# Sheet3.net
KiCad netlist of a schematic drawn in Altium Designer
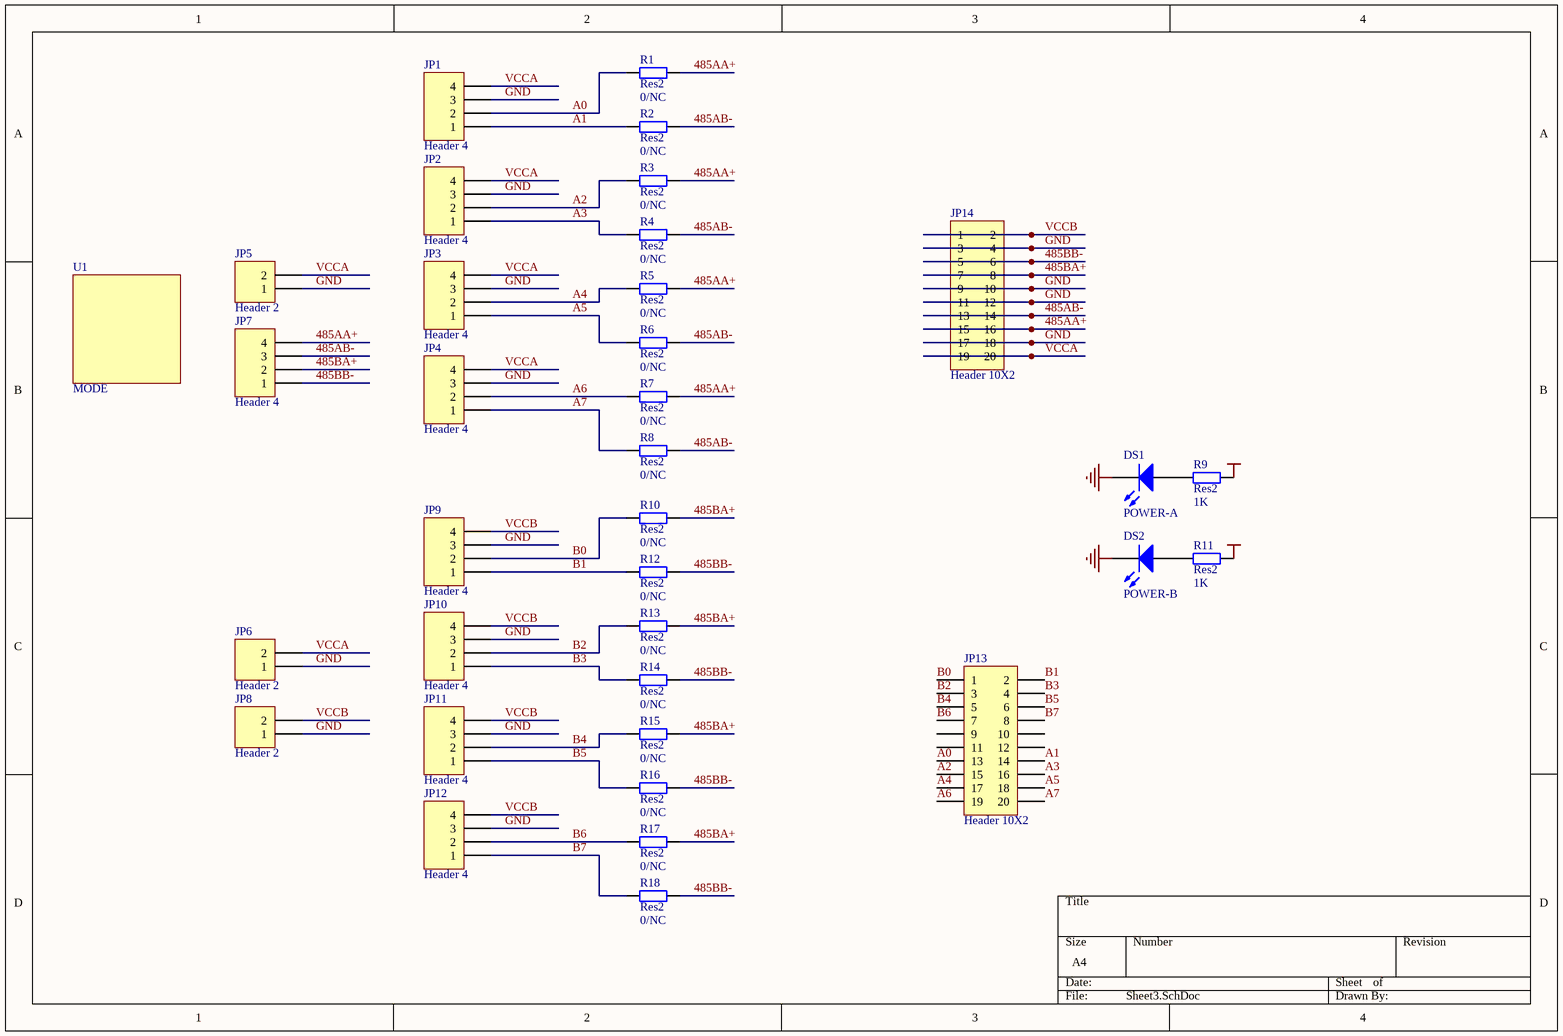
[diagram p0: Sheet3.SchDoc]

(export (version "E")
  (design (tool "Eeschema 10.0.6"))
  (components
    (comp (ref "DS1")
      (value "POWER-A")
      (footprint "SMD _LED")
      (description "Typical BLUE SiC LED")
      (fields (field (name "PUBLISHER") "Altium Limited"))
      (libsource (lib "Miscellaneous Devices") (part "LED3"))
    )
    (comp (ref "DS2")
      (value "POWER-B")
      (footprint "SMD _LED")
      (description "Typical BLUE SiC LED")
      (fields (field (name "PUBLISHER") "Altium Limited"))
      (libsource (lib "Miscellaneous Devices") (part "LED3"))
    )
    (comp (ref "JP1")
      (value "Header 4")
      (footprint "duanzi-4")
      (description "Header, 4-Pin")
      (fields (field (name "PUBLISHER") "Altium Limited"))
      (libsource (lib "Miscellaneous Connectors") (part "Header 4"))
    )
    (comp (ref "JP2")
      (value "Header 4")
      (footprint "duanzi-4")
      (description "Header, 4-Pin")
      (fields (field (name "PUBLISHER") "Altium Limited"))
      (libsource (lib "Miscellaneous Connectors") (part "Header 4"))
    )
    (comp (ref "JP3")
      (value "Header 4")
      (footprint "duanzi-4")
      (description "Header, 4-Pin")
      (fields (field (name "PUBLISHER") "Altium Limited"))
      (libsource (lib "Miscellaneous Connectors") (part "Header 4"))
    )
    (comp (ref "JP4")
      (value "Header 4")
      (footprint "duanzi-4")
      (description "Header, 4-Pin")
      (fields (field (name "PUBLISHER") "Altium Limited"))
      (libsource (lib "Miscellaneous Connectors") (part "Header 4"))
    )
    (comp (ref "JP5")
      (value "Header 2")
      (footprint "duanzi-2")
      (description "Header, 2-Pin")
      (fields (field (name "PUBLISHER") "Altium Limited"))
      (libsource (lib "Miscellaneous Connectors") (part "Header 2"))
    )
    (comp (ref "JP6")
      (value "Header 2")
      (footprint "duanzi-2")
      (description "Header, 2-Pin")
      (fields (field (name "PUBLISHER") "Altium Limited"))
      (libsource (lib "Miscellaneous Connectors") (part "Header 2"))
    )
    (comp (ref "JP7")
      (value "Header 4")
      (footprint "duanzi-4")
      (description "Header, 4-Pin")
      (fields (field (name "PUBLISHER") "Altium Limited"))
      (libsource (lib "Miscellaneous Connectors") (part "Header 4"))
    )
    (comp (ref "JP8")
      (value "Header 2")
      (footprint "duanzi-2")
      (description "Header, 2-Pin")
      (fields (field (name "PUBLISHER") "Altium Limited"))
      (libsource (lib "Miscellaneous Connectors") (part "Header 2"))
    )
    (comp (ref "JP9")
      (value "Header 4")
      (footprint "duanzi-4")
      (description "Header, 4-Pin")
      (fields (field (name "PUBLISHER") "Altium Limited"))
      (libsource (lib "Miscellaneous Connectors") (part "Header 4"))
    )
    (comp (ref "JP10")
      (value "Header 4")
      (footprint "duanzi-4")
      (description "Header, 4-Pin")
      (fields (field (name "PUBLISHER") "Altium Limited"))
      (libsource (lib "Miscellaneous Connectors") (part "Header 4"))
    )
    (comp (ref "JP11")
      (value "Header 4")
      (footprint "duanzi-4")
      (description "Header, 4-Pin")
      (fields (field (name "PUBLISHER") "Altium Limited"))
      (libsource (lib "Miscellaneous Connectors") (part "Header 4"))
    )
    (comp (ref "JP12")
      (value "Header 4")
      (footprint "duanzi-4")
      (description "Header, 4-Pin")
      (fields (field (name "PUBLISHER") "Altium Limited"))
      (libsource (lib "Miscellaneous Connectors") (part "Header 4"))
    )
    (comp (ref "JP13")
      (value "Header 10X2")
      (footprint "HDR2X10")
      (description "Header, 10-Pin, Dual row")
      (fields (field (name "PUBLISHER") "Altium Limited"))
      (libsource (lib "Miscellaneous Connectors") (part "Header 10X2"))
    )
    (comp (ref "JP14")
      (value "Header 10X2")
      (footprint "HDR2X10")
      (description "Header, 10-Pin, Dual row")
      (fields (field (name "PUBLISHER") "Altium Limited"))
      (libsource (lib "Miscellaneous Connectors") (part "Header 10X2"))
    )
    (comp (ref "R1")
      (value "Res2")
      (footprint "1206")
      (description "Resistor")
      (fields (field (name "ALTIUM_VALUE") "0/NC") (field (name "PUBLISHER") "Altium Limited"))
      (libsource (lib "Miscellaneous Devices") (part "Res2"))
    )
    (comp (ref "R2")
      (value "Res2")
      (footprint "1206")
      (description "Resistor")
      (fields (field (name "ALTIUM_VALUE") "0/NC") (field (name "PUBLISHER") "Altium Limited"))
      (libsource (lib "Miscellaneous Devices") (part "Res2"))
    )
    (comp (ref "R3")
      (value "Res2")
      (footprint "1206")
      (description "Resistor")
      (fields (field (name "ALTIUM_VALUE") "0/NC") (field (name "PUBLISHER") "Altium Limited"))
      (libsource (lib "Miscellaneous Devices") (part "Res2"))
    )
    (comp (ref "R4")
      (value "Res2")
      (footprint "1206")
      (description "Resistor")
      (fields (field (name "ALTIUM_VALUE") "0/NC") (field (name "PUBLISHER") "Altium Limited"))
      (libsource (lib "Miscellaneous Devices") (part "Res2"))
    )
    (comp (ref "R5")
      (value "Res2")
      (footprint "1206")
      (description "Resistor")
      (fields (field (name "ALTIUM_VALUE") "0/NC") (field (name "PUBLISHER") "Altium Limited"))
      (libsource (lib "Miscellaneous Devices") (part "Res2"))
    )
    (comp (ref "R6")
      (value "Res2")
      (footprint "1206")
      (description "Resistor")
      (fields (field (name "ALTIUM_VALUE") "0/NC") (field (name "PUBLISHER") "Altium Limited"))
      (libsource (lib "Miscellaneous Devices") (part "Res2"))
    )
    (comp (ref "R7")
      (value "Res2")
      (footprint "1206")
      (description "Resistor")
      (fields (field (name "ALTIUM_VALUE") "0/NC") (field (name "PUBLISHER") "Altium Limited"))
      (libsource (lib "Miscellaneous Devices") (part "Res2"))
    )
    (comp (ref "R8")
      (value "Res2")
      (footprint "1206")
      (description "Resistor")
      (fields (field (name "ALTIUM_VALUE") "0/NC") (field (name "PUBLISHER") "Altium Limited"))
      (libsource (lib "Miscellaneous Devices") (part "Res2"))
    )
    (comp (ref "R9")
      (value "Res2")
      (footprint "1206")
      (description "Resistor")
      (fields (field (name "ALTIUM_VALUE") "1K") (field (name "PUBLISHER") "Altium Limited"))
      (libsource (lib "") (part "Res2_1"))
    )
    (comp (ref "R10")
      (value "Res2")
      (footprint "1206")
      (description "Resistor")
      (fields (field (name "ALTIUM_VALUE") "0/NC") (field (name "PUBLISHER") "Altium Limited"))
      (libsource (lib "Miscellaneous Devices") (part "Res2"))
    )
    (comp (ref "R11")
      (value "Res2")
      (footprint "1206")
      (description "Resistor")
      (fields (field (name "ALTIUM_VALUE") "1K") (field (name "PUBLISHER") "Altium Limited"))
      (libsource (lib "") (part "Res2_1"))
    )
    (comp (ref "R12")
      (value "Res2")
      (footprint "1206")
      (description "Resistor")
      (fields (field (name "ALTIUM_VALUE") "0/NC") (field (name "PUBLISHER") "Altium Limited"))
      (libsource (lib "Miscellaneous Devices") (part "Res2"))
    )
    (comp (ref "R13")
      (value "Res2")
      (footprint "1206")
      (description "Resistor")
      (fields (field (name "ALTIUM_VALUE") "0/NC") (field (name "PUBLISHER") "Altium Limited"))
      (libsource (lib "Miscellaneous Devices") (part "Res2"))
    )
    (comp (ref "R14")
      (value "Res2")
      (footprint "1206")
      (description "Resistor")
      (fields (field (name "ALTIUM_VALUE") "0/NC") (field (name "PUBLISHER") "Altium Limited"))
      (libsource (lib "Miscellaneous Devices") (part "Res2"))
    )
    (comp (ref "R15")
      (value "Res2")
      (footprint "1206")
      (description "Resistor")
      (fields (field (name "ALTIUM_VALUE") "0/NC") (field (name "PUBLISHER") "Altium Limited"))
      (libsource (lib "Miscellaneous Devices") (part "Res2"))
    )
    (comp (ref "R16")
      (value "Res2")
      (footprint "1206")
      (description "Resistor")
      (fields (field (name "ALTIUM_VALUE") "0/NC") (field (name "PUBLISHER") "Altium Limited"))
      (libsource (lib "Miscellaneous Devices") (part "Res2"))
    )
    (comp (ref "R17")
      (value "Res2")
      (footprint "1206")
      (description "Resistor")
      (fields (field (name "ALTIUM_VALUE") "0/NC") (field (name "PUBLISHER") "Altium Limited"))
      (libsource (lib "Miscellaneous Devices") (part "Res2"))
    )
    (comp (ref "R18")
      (value "Res2")
      (footprint "1206")
      (description "Resistor")
      (fields (field (name "ALTIUM_VALUE") "0/NC") (field (name "PUBLISHER") "Altium Limited"))
      (libsource (lib "Miscellaneous Devices") (part "Res2"))
    )
    (comp (ref "U1")
      (value "MODE")
      (footprint "sw-tcpip")
      (description "Generic Phase Locked Loop")
      (fields (field (name "PUBLISHER") "Altium Limited"))
      (libsource (lib "Miscellaneous Devices") (part "PLL"))
    )
  )
  (nets
    (net (code "1") (name "/485AA+") (class "Default")
      (node (ref "JP14") (pin "15") (pinfunction "15_15") (pintype "passive"))
      (node (ref "JP14") (pin "16") (pinfunction "16_16") (pintype "passive"))
      (node (ref "JP7") (pin "4") (pinfunction "4_4") (pintype "passive"))
      (node (ref "R1") (pin "1") (pinfunction "1_1") (pintype "passive"))
      (node (ref "R3") (pin "1") (pinfunction "1_1") (pintype "passive"))
      (node (ref "R5") (pin "1") (pinfunction "1_1") (pintype "passive"))
      (node (ref "R7") (pin "1") (pinfunction "1_1") (pintype "passive"))
    )
    (net (code "2") (name "/485AB-") (class "Default")
      (node (ref "JP14") (pin "13") (pinfunction "13_13") (pintype "passive"))
      (node (ref "JP14") (pin "14") (pinfunction "14_14") (pintype "passive"))
      (node (ref "JP7") (pin "3") (pinfunction "3_3") (pintype "passive"))
      (node (ref "R2") (pin "1") (pinfunction "1_1") (pintype "passive"))
      (node (ref "R4") (pin "1") (pinfunction "1_1") (pintype "passive"))
      (node (ref "R6") (pin "1") (pinfunction "1_1") (pintype "passive"))
      (node (ref "R8") (pin "1") (pinfunction "1_1") (pintype "passive"))
    )
    (net (code "3") (name "/485BA+") (class "Default")
      (node (ref "JP14") (pin "7") (pinfunction "7_7") (pintype "passive"))
      (node (ref "JP14") (pin "8") (pinfunction "8_8") (pintype "passive"))
      (node (ref "JP7") (pin "2") (pinfunction "2_2") (pintype "passive"))
      (node (ref "R10") (pin "1") (pinfunction "1_1") (pintype "passive"))
      (node (ref "R13") (pin "1") (pinfunction "1_1") (pintype "passive"))
      (node (ref "R15") (pin "1") (pinfunction "1_1") (pintype "passive"))
      (node (ref "R17") (pin "1") (pinfunction "1_1") (pintype "passive"))
    )
    (net (code "4") (name "/485BB-") (class "Default")
      (node (ref "JP14") (pin "5") (pinfunction "5_5") (pintype "passive"))
      (node (ref "JP14") (pin "6") (pinfunction "6_6") (pintype "passive"))
      (node (ref "JP7") (pin "1") (pinfunction "1_1") (pintype "passive"))
      (node (ref "R12") (pin "1") (pinfunction "1_1") (pintype "passive"))
      (node (ref "R14") (pin "1") (pinfunction "1_1") (pintype "passive"))
      (node (ref "R16") (pin "1") (pinfunction "1_1") (pintype "passive"))
      (node (ref "R18") (pin "1") (pinfunction "1_1") (pintype "passive"))
    )
    (net (code "5") (name "/A0") (class "Default")
      (node (ref "JP1") (pin "2") (pinfunction "2_2") (pintype "passive"))
      (node (ref "JP13") (pin "13") (pinfunction "13_13") (pintype "passive"))
      (node (ref "R1") (pin "2") (pinfunction "2_2") (pintype "passive"))
    )
    (net (code "6") (name "/A1") (class "Default")
      (node (ref "JP1") (pin "1") (pinfunction "1_1") (pintype "passive"))
      (node (ref "JP13") (pin "14") (pinfunction "14_14") (pintype "passive"))
      (node (ref "R2") (pin "2") (pinfunction "2_2") (pintype "passive"))
    )
    (net (code "7") (name "/A2") (class "Default")
      (node (ref "JP13") (pin "15") (pinfunction "15_15") (pintype "passive"))
      (node (ref "JP2") (pin "2") (pinfunction "2_2") (pintype "passive"))
      (node (ref "R3") (pin "2") (pinfunction "2_2") (pintype "passive"))
    )
    (net (code "8") (name "/A3") (class "Default")
      (node (ref "JP13") (pin "16") (pinfunction "16_16") (pintype "passive"))
      (node (ref "JP2") (pin "1") (pinfunction "1_1") (pintype "passive"))
      (node (ref "R4") (pin "2") (pinfunction "2_2") (pintype "passive"))
    )
    (net (code "9") (name "/A4") (class "Default")
      (node (ref "JP13") (pin "17") (pinfunction "17_17") (pintype "passive"))
      (node (ref "JP3") (pin "2") (pinfunction "2_2") (pintype "passive"))
      (node (ref "R5") (pin "2") (pinfunction "2_2") (pintype "passive"))
    )
    (net (code "10") (name "/A5") (class "Default")
      (node (ref "JP13") (pin "18") (pinfunction "18_18") (pintype "passive"))
      (node (ref "JP3") (pin "1") (pinfunction "1_1") (pintype "passive"))
      (node (ref "R6") (pin "2") (pinfunction "2_2") (pintype "passive"))
    )
    (net (code "11") (name "/A6") (class "Default")
      (node (ref "JP13") (pin "19") (pinfunction "19_19") (pintype "passive"))
      (node (ref "JP4") (pin "2") (pinfunction "2_2") (pintype "passive"))
      (node (ref "R7") (pin "2") (pinfunction "2_2") (pintype "passive"))
    )
    (net (code "12") (name "/A7") (class "Default")
      (node (ref "JP13") (pin "20") (pinfunction "20_20") (pintype "passive"))
      (node (ref "JP4") (pin "1") (pinfunction "1_1") (pintype "passive"))
      (node (ref "R8") (pin "2") (pinfunction "2_2") (pintype "passive"))
    )
    (net (code "13") (name "/B0") (class "Default")
      (node (ref "JP13") (pin "1") (pinfunction "1_1") (pintype "passive"))
      (node (ref "JP9") (pin "2") (pinfunction "2_2") (pintype "passive"))
      (node (ref "R10") (pin "2") (pinfunction "2_2") (pintype "passive"))
    )
    (net (code "14") (name "/B1") (class "Default")
      (node (ref "JP13") (pin "2") (pinfunction "2_2") (pintype "passive"))
      (node (ref "JP9") (pin "1") (pinfunction "1_1") (pintype "passive"))
      (node (ref "R12") (pin "2") (pinfunction "2_2") (pintype "passive"))
    )
    (net (code "15") (name "/B2") (class "Default")
      (node (ref "JP10") (pin "2") (pinfunction "2_2") (pintype "passive"))
      (node (ref "JP13") (pin "3") (pinfunction "3_3") (pintype "passive"))
      (node (ref "R13") (pin "2") (pinfunction "2_2") (pintype "passive"))
    )
    (net (code "16") (name "/B3") (class "Default")
      (node (ref "JP10") (pin "1") (pinfunction "1_1") (pintype "passive"))
      (node (ref "JP13") (pin "4") (pinfunction "4_4") (pintype "passive"))
      (node (ref "R14") (pin "2") (pinfunction "2_2") (pintype "passive"))
    )
    (net (code "17") (name "/B4") (class "Default")
      (node (ref "JP11") (pin "2") (pinfunction "2_2") (pintype "passive"))
      (node (ref "JP13") (pin "5") (pinfunction "5_5") (pintype "passive"))
      (node (ref "R15") (pin "2") (pinfunction "2_2") (pintype "passive"))
    )
    (net (code "18") (name "/B5") (class "Default")
      (node (ref "JP11") (pin "1") (pinfunction "1_1") (pintype "passive"))
      (node (ref "JP13") (pin "6") (pinfunction "6_6") (pintype "passive"))
      (node (ref "R16") (pin "2") (pinfunction "2_2") (pintype "passive"))
    )
    (net (code "19") (name "/B6") (class "Default")
      (node (ref "JP12") (pin "2") (pinfunction "2_2") (pintype "passive"))
      (node (ref "JP13") (pin "7") (pinfunction "7_7") (pintype "passive"))
      (node (ref "R17") (pin "2") (pinfunction "2_2") (pintype "passive"))
    )
    (net (code "20") (name "/B7") (class "Default")
      (node (ref "JP12") (pin "1") (pinfunction "1_1") (pintype "passive"))
      (node (ref "JP13") (pin "8") (pinfunction "8_8") (pintype "passive"))
      (node (ref "R18") (pin "2") (pinfunction "2_2") (pintype "passive"))
    )
    (net (code "21") (name "GND") (class "Default")
      (node (ref "DS1") (pin "2") (pinfunction "K_2") (pintype "passive"))
      (node (ref "DS2") (pin "2") (pinfunction "K_2") (pintype "passive"))
      (node (ref "JP1") (pin "3") (pinfunction "3_3") (pintype "passive"))
      (node (ref "JP10") (pin "3") (pinfunction "3_3") (pintype "passive"))
      (node (ref "JP11") (pin "3") (pinfunction "3_3") (pintype "passive"))
      (node (ref "JP12") (pin "3") (pinfunction "3_3") (pintype "passive"))
      (node (ref "JP14") (pin "10") (pinfunction "10_10") (pintype "passive"))
      (node (ref "JP14") (pin "11") (pinfunction "11_11") (pintype "passive"))
      (node (ref "JP14") (pin "12") (pinfunction "12_12") (pintype "passive"))
      (node (ref "JP14") (pin "17") (pinfunction "17_17") (pintype "passive"))
      (node (ref "JP14") (pin "18") (pinfunction "18_18") (pintype "passive"))
      (node (ref "JP14") (pin "3") (pinfunction "3_3") (pintype "passive"))
      (node (ref "JP14") (pin "4") (pinfunction "4_4") (pintype "passive"))
      (node (ref "JP14") (pin "9") (pinfunction "9_9") (pintype "passive"))
      (node (ref "JP2") (pin "3") (pinfunction "3_3") (pintype "passive"))
      (node (ref "JP3") (pin "3") (pinfunction "3_3") (pintype "passive"))
      (node (ref "JP4") (pin "3") (pinfunction "3_3") (pintype "passive"))
      (node (ref "JP5") (pin "1") (pinfunction "1_1") (pintype "passive"))
      (node (ref "JP6") (pin "1") (pinfunction "1_1") (pintype "passive"))
      (node (ref "JP8") (pin "1") (pinfunction "1_1") (pintype "passive"))
      (node (ref "JP9") (pin "3") (pinfunction "3_3") (pintype "passive"))
    )
    (net (code "22") (name "Net-(DS1-A)") (class "Default")
      (node (ref "DS1") (pin "1") (pinfunction "A_1") (pintype "passive"))
      (node (ref "R9") (pin "1") (pinfunction "1_1") (pintype "passive"))
    )
    (net (code "23") (name "Net-(DS2-A)") (class "Default")
      (node (ref "DS2") (pin "1") (pinfunction "A_1") (pintype "passive"))
      (node (ref "R11") (pin "1") (pinfunction "1_1") (pintype "passive"))
    )
    (net (code "24") (name "VCCA") (class "Default")
      (node (ref "JP1") (pin "4") (pinfunction "4_4") (pintype "passive"))
      (node (ref "JP14") (pin "19") (pinfunction "19_19") (pintype "passive"))
      (node (ref "JP14") (pin "20") (pinfunction "20_20") (pintype "passive"))
      (node (ref "JP2") (pin "4") (pinfunction "4_4") (pintype "passive"))
      (node (ref "JP3") (pin "4") (pinfunction "4_4") (pintype "passive"))
      (node (ref "JP4") (pin "4") (pinfunction "4_4") (pintype "passive"))
      (node (ref "JP5") (pin "2") (pinfunction "2_2") (pintype "passive"))
      (node (ref "JP6") (pin "2") (pinfunction "2_2") (pintype "passive"))
      (node (ref "R9") (pin "2") (pinfunction "2_2") (pintype "passive"))
    )
    (net (code "25") (name "VCCB") (class "Default")
      (node (ref "JP10") (pin "4") (pinfunction "4_4") (pintype "passive"))
      (node (ref "JP11") (pin "4") (pinfunction "4_4") (pintype "passive"))
      (node (ref "JP12") (pin "4") (pinfunction "4_4") (pintype "passive"))
      (node (ref "JP14") (pin "1") (pinfunction "1_1") (pintype "passive"))
      (node (ref "JP14") (pin "2") (pinfunction "2_2") (pintype "passive"))
      (node (ref "JP8") (pin "2") (pinfunction "2_2") (pintype "passive"))
      (node (ref "JP9") (pin "4") (pinfunction "4_4") (pintype "passive"))
      (node (ref "R11") (pin "2") (pinfunction "2_2") (pintype "passive"))
    )
    (net (code "26") (name "unconnected-(JP13-Pad9)") (class "Default")
      (node (ref "JP13") (pin "9") (pinfunction "9_9") (pintype "passive"))
    )
    (net (code "27") (name "unconnected-(JP13-Pad10)") (class "Default")
      (node (ref "JP13") (pin "10") (pinfunction "10_10") (pintype "passive"))
    )
    (net (code "28") (name "unconnected-(JP13-Pad11)") (class "Default")
      (node (ref "JP13") (pin "11") (pinfunction "11_11") (pintype "passive"))
    )
    (net (code "29") (name "unconnected-(JP13-Pad12)") (class "Default")
      (node (ref "JP13") (pin "12") (pinfunction "12_12") (pintype "passive"))
    )
  )
)
